# Source_Selection.net
KiCad netlist of a schematic drawn in Altium Designer
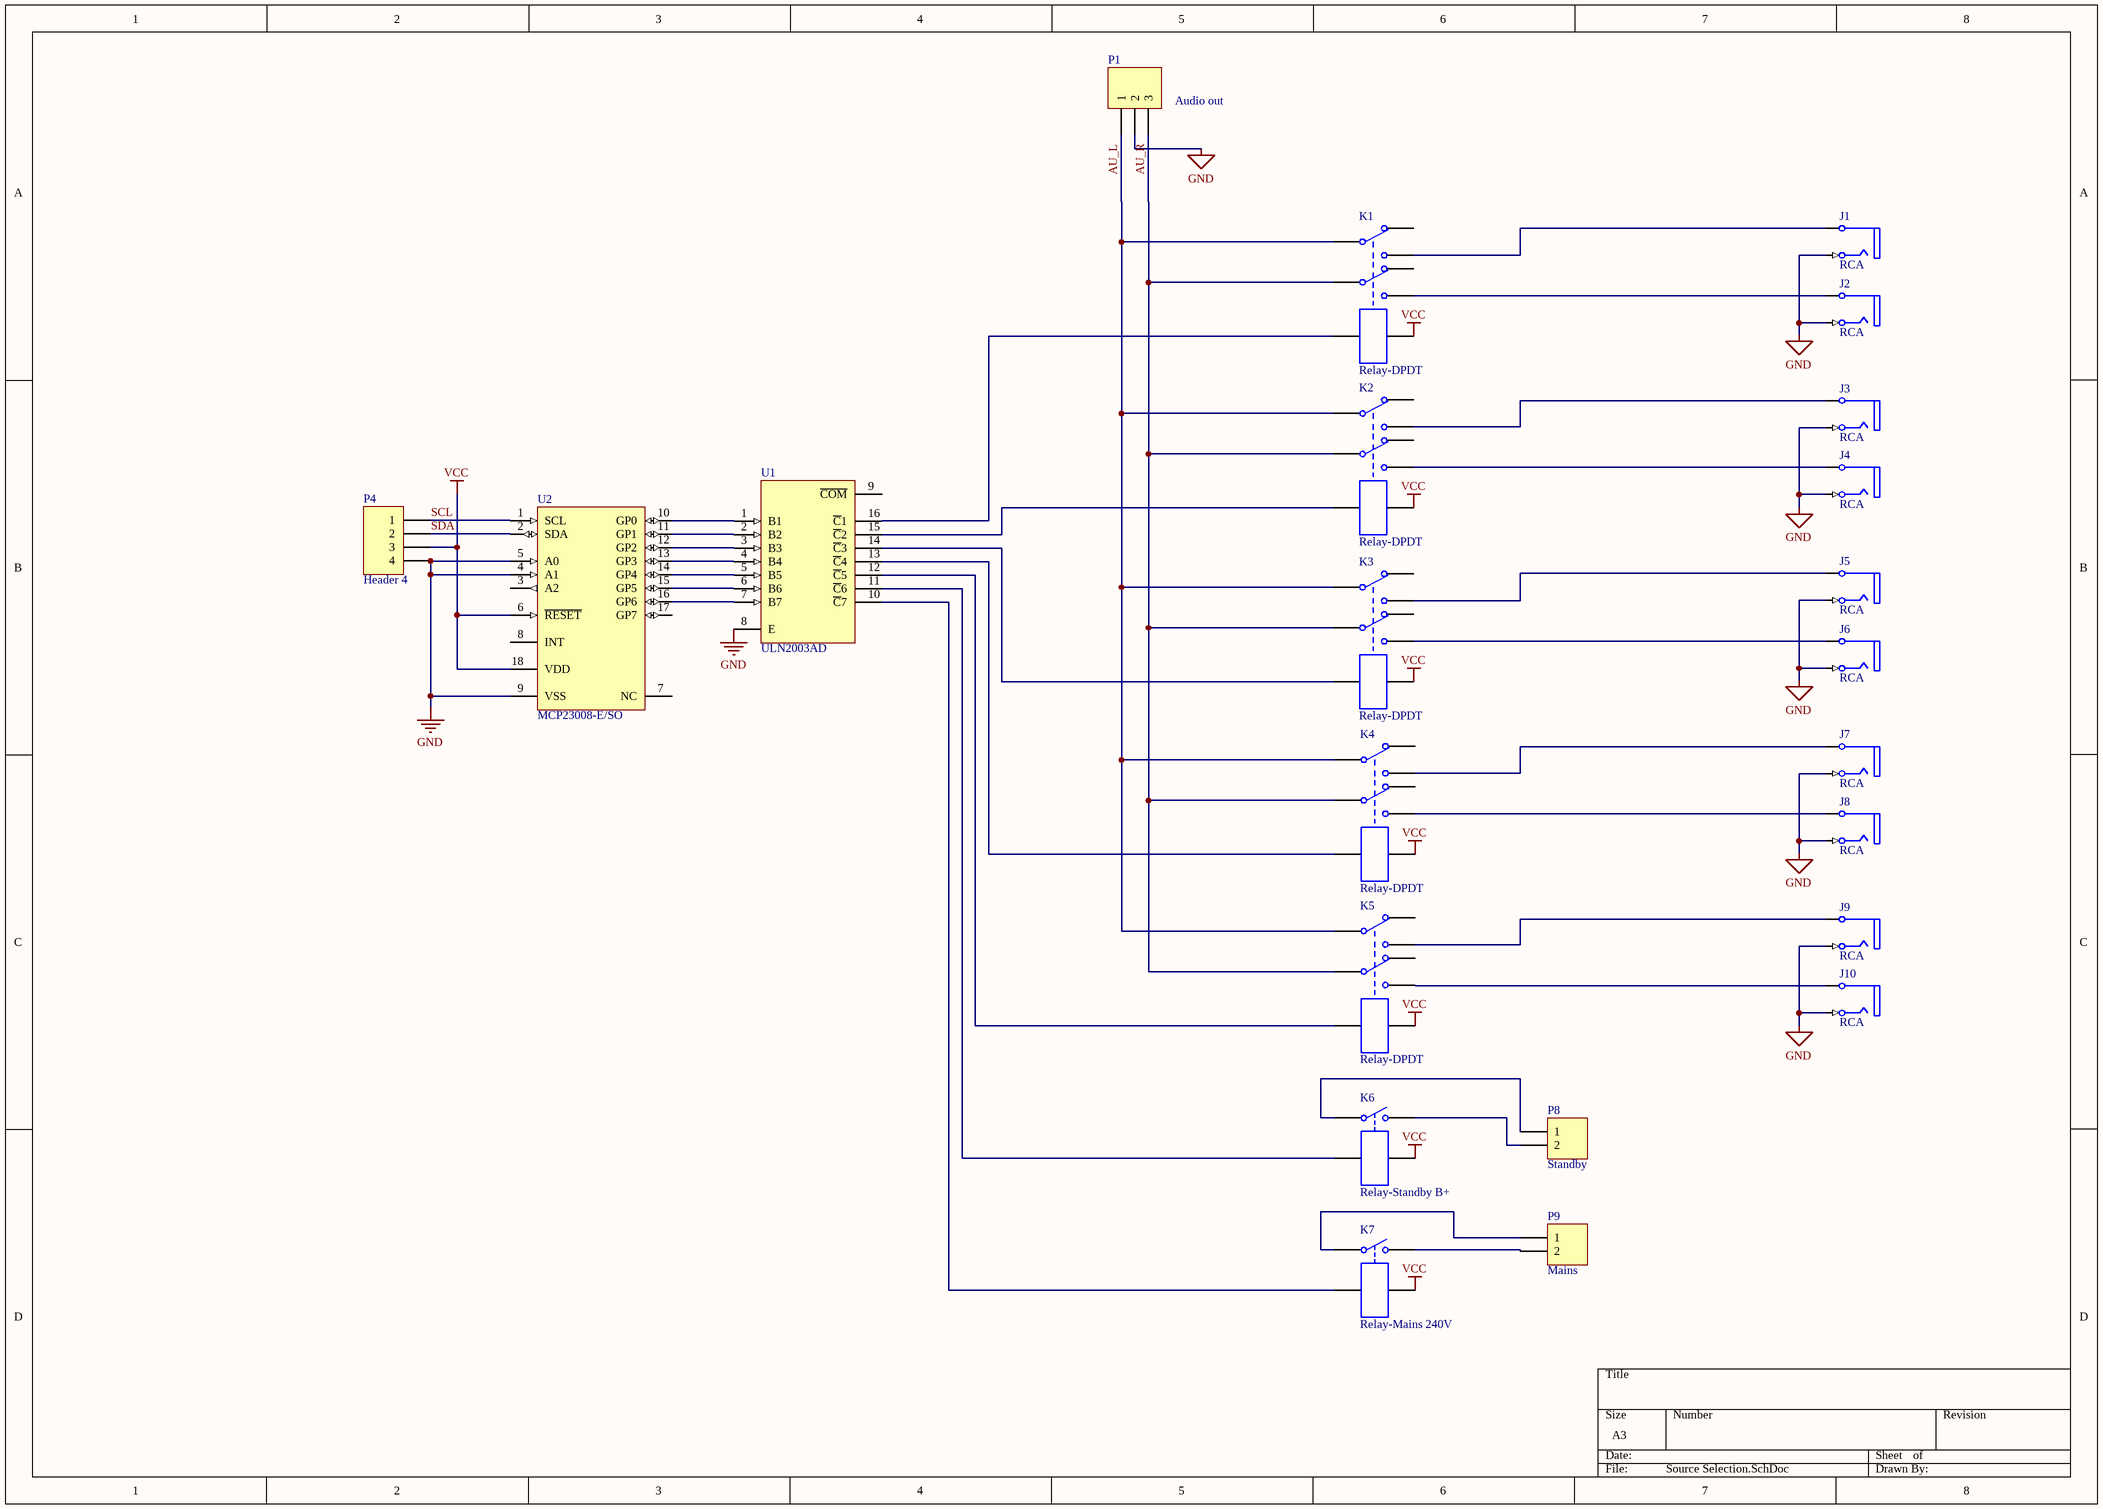
[diagram p0: Source Selection.SchDoc]

(export (version "E")
  (design (tool "Eeschema 10.0.6"))
  (components
    (comp (ref "J1")
      (value "RCA")
      (footprint "RCA/4.5-H2")
      (description "RCA Phono Jack, Right Angle, Thru-Hole, Snap-In")
      (fields (field (name "PUBLISHER") "Altium Limited"))
      (libsource (lib "Miscellaneous Connectors") (part "RCA"))
    )
    (comp (ref "J2")
      (value "RCA")
      (footprint "RCA/4.5-H2")
      (description "RCA Phono Jack, Right Angle, Thru-Hole, Snap-In")
      (fields (field (name "PUBLISHER") "Altium Limited"))
      (libsource (lib "Miscellaneous Connectors") (part "RCA"))
    )
    (comp (ref "J3")
      (value "RCA")
      (footprint "RCA/4.5-H2")
      (description "RCA Phono Jack, Right Angle, Thru-Hole, Snap-In")
      (fields (field (name "PUBLISHER") "Altium Limited"))
      (libsource (lib "Miscellaneous Connectors") (part "RCA"))
    )
    (comp (ref "J4")
      (value "RCA")
      (footprint "RCA/4.5-H2")
      (description "RCA Phono Jack, Right Angle, Thru-Hole, Snap-In")
      (fields (field (name "PUBLISHER") "Altium Limited"))
      (libsource (lib "Miscellaneous Connectors") (part "RCA"))
    )
    (comp (ref "J5")
      (value "RCA")
      (footprint "RCA/4.5-H2")
      (description "RCA Phono Jack, Right Angle, Thru-Hole, Snap-In")
      (fields (field (name "PUBLISHER") "Altium Limited"))
      (libsource (lib "Miscellaneous Connectors") (part "RCA"))
    )
    (comp (ref "J6")
      (value "RCA")
      (footprint "RCA/4.5-H2")
      (description "RCA Phono Jack, Right Angle, Thru-Hole, Snap-In")
      (fields (field (name "PUBLISHER") "Altium Limited"))
      (libsource (lib "Miscellaneous Connectors") (part "RCA"))
    )
    (comp (ref "J7")
      (value "RCA")
      (footprint "RCA/4.5-H2")
      (description "RCA Phono Jack, Right Angle, Thru-Hole, Snap-In")
      (fields (field (name "PUBLISHER") "Altium Limited"))
      (libsource (lib "Miscellaneous Connectors") (part "RCA"))
    )
    (comp (ref "J8")
      (value "RCA")
      (footprint "RCA/4.5-H2")
      (description "RCA Phono Jack, Right Angle, Thru-Hole, Snap-In")
      (fields (field (name "PUBLISHER") "Altium Limited"))
      (libsource (lib "Miscellaneous Connectors") (part "RCA"))
    )
    (comp (ref "J9")
      (value "RCA")
      (footprint "RCA/4.5-H2")
      (description "RCA Phono Jack, Right Angle, Thru-Hole, Snap-In")
      (fields (field (name "PUBLISHER") "Altium Limited"))
      (libsource (lib "Miscellaneous Connectors") (part "RCA"))
    )
    (comp (ref "J10")
      (value "RCA")
      (footprint "RCA/4.5-H2")
      (description "RCA Phono Jack, Right Angle, Thru-Hole, Snap-In")
      (fields (field (name "PUBLISHER") "Altium Limited"))
      (libsource (lib "Miscellaneous Connectors") (part "RCA"))
    )
    (comp (ref "K1")
      (value "Relay-DPDT")
      (footprint "DIP-P8")
      (description "Dual-Pole Dual-Throw Relay")
      (fields (field (name "PUBLISHER") "Altium Limited"))
      (libsource (lib "Miscellaneous Devices") (part "Relay-DPDT"))
    )
    (comp (ref "K2")
      (value "Relay-DPDT")
      (footprint "DIP-P8")
      (description "Dual-Pole Dual-Throw Relay")
      (fields (field (name "PUBLISHER") "Altium Limited"))
      (libsource (lib "Miscellaneous Devices") (part "Relay-DPDT"))
    )
    (comp (ref "K3")
      (value "Relay-DPDT")
      (footprint "DIP-P8")
      (description "Dual-Pole Dual-Throw Relay")
      (fields (field (name "PUBLISHER") "Altium Limited"))
      (libsource (lib "Miscellaneous Devices") (part "Relay-DPDT"))
    )
    (comp (ref "K4")
      (value "Relay-DPDT")
      (footprint "DIP-P8")
      (description "Dual-Pole Dual-Throw Relay")
      (fields (field (name "PUBLISHER") "Altium Limited"))
      (libsource (lib "Miscellaneous Devices") (part "Relay-DPDT"))
    )
    (comp (ref "K5")
      (value "Relay-DPDT")
      (footprint "DIP-P8")
      (description "Dual-Pole Dual-Throw Relay")
      (fields (field (name "PUBLISHER") "Altium Limited"))
      (libsource (lib "Miscellaneous Devices") (part "Relay-DPDT"))
    )
    (comp (ref "K6")
      (value "Relay-Standby B+")
      (footprint "MODULE4")
      (description "Single-Pole Single-Throw Relay")
      (fields (field (name "PUBLISHER") "Altium Limited"))
      (libsource (lib "Miscellaneous Devices") (part "Relay-SPST"))
    )
    (comp (ref "K7")
      (value "Relay-Mains 240V")
      (footprint "MODULE4")
      (description "Single-Pole Single-Throw Relay")
      (fields (field (name "PUBLISHER") "Altium Limited"))
      (libsource (lib "Miscellaneous Devices") (part "Relay-SPST"))
    )
    (comp (ref "P1")
      (value "Audio out")
      (footprint "PH_TERM_3")
      (description "Header, 3-Pin")
      (fields (field (name "PUBLISHER") "Altium Limited"))
      (libsource (lib "Miscellaneous Connectors") (part "Header 3"))
    )
    (comp (ref "P4")
      (value "Header 4")
      (footprint "IDC2.54-H10C")
      (description "Header, 4-Pin")
      (fields (field (name "PUBLISHER") "Altium Limited"))
      (libsource (lib "Miscellaneous Connectors") (part "Header 4"))
    )
    (comp (ref "P8")
      (value "Standby")
      (footprint "PH_TERM_2")
      (description "Header, 2-Pin")
      (fields (field (name "PUBLISHER") "Altium Limited"))
      (libsource (lib "Miscellaneous Connectors") (part "Header 2"))
    )
    (comp (ref "P9")
      (value "Mains")
      (footprint "HDR1X2")
      (description "Header, 2-Pin")
      (fields (field (name "PUBLISHER") "Altium Limited"))
      (libsource (lib "Miscellaneous Connectors") (part "Header 2"))
    )
    (comp (ref "U1")
      (value "ULN2003AD")
      (footprint "D016_N")
      (description "Darlington Transistor Array")
      (fields (field (name "PUBLISHER") "Altium Limited"))
      (libsource (lib "TI Interface Darlington Driver") (part "ULN2003AD"))
    )
    (comp (ref "U2")
      (value "MCP23008-E/SO")
      (footprint "SOIC-SO18_N")
      (description "8-Bit I/O Expander with Serial Interface, 18-Pin SOIC, Extended Temperature")
      (fields (field (name "PUBLISHER") "Altium Limited"))
      (libsource (lib "Microchip Interface") (part "MCP23008-E/SO"))
    )
  )
  (nets
    (net (code "1") (name "/AU_L") (class "Default")
      (node (ref "K1") (pin "1") (pinfunction "1_1") (pintype "passive"))
      (node (ref "K2") (pin "1") (pinfunction "1_1") (pintype "passive"))
      (node (ref "K3") (pin "1") (pinfunction "1_1") (pintype "passive"))
      (node (ref "K4") (pin "1") (pinfunction "1_1") (pintype "passive"))
      (node (ref "K5") (pin "1") (pinfunction "1_1") (pintype "passive"))
      (node (ref "P1") (pin "1") (pinfunction "1_1") (pintype "passive"))
    )
    (net (code "2") (name "/AU_R") (class "Default")
      (node (ref "K1") (pin "4") (pinfunction "4_4") (pintype "passive"))
      (node (ref "K2") (pin "4") (pinfunction "4_4") (pintype "passive"))
      (node (ref "K3") (pin "4") (pinfunction "4_4") (pintype "passive"))
      (node (ref "K4") (pin "4") (pinfunction "4_4") (pintype "passive"))
      (node (ref "K5") (pin "4") (pinfunction "4_4") (pintype "passive"))
      (node (ref "P1") (pin "3") (pinfunction "3_3") (pintype "passive"))
    )
    (net (code "3") (name "/SCL") (class "Default")
      (node (ref "P4") (pin "1") (pinfunction "1_1") (pintype "passive"))
      (node (ref "U2") (pin "1") (pinfunction "SCL_1") (pintype "input"))
    )
    (net (code "4") (name "/SDA") (class "Default")
      (node (ref "P4") (pin "2") (pinfunction "2_2") (pintype "passive"))
      (node (ref "U2") (pin "2") (pinfunction "SDA_2") (pintype "bidirectional"))
    )
    (net (code "5") (name "GND") (class "Default")
      (node (ref "J1") (pin "2B") (pinfunction "Signal_2B") (pintype "input"))
      (node (ref "J10") (pin "2B") (pinfunction "Signal_2B") (pintype "input"))
      (node (ref "J2") (pin "2B") (pinfunction "Signal_2B") (pintype "input"))
      (node (ref "J3") (pin "2B") (pinfunction "Signal_2B") (pintype "input"))
      (node (ref "J4") (pin "2B") (pinfunction "Signal_2B") (pintype "input"))
      (node (ref "J5") (pin "2B") (pinfunction "Signal_2B") (pintype "input"))
      (node (ref "J6") (pin "2B") (pinfunction "Signal_2B") (pintype "input"))
      (node (ref "J7") (pin "2B") (pinfunction "Signal_2B") (pintype "input"))
      (node (ref "J8") (pin "2B") (pinfunction "Signal_2B") (pintype "input"))
      (node (ref "J9") (pin "2B") (pinfunction "Signal_2B") (pintype "input"))
      (node (ref "P1") (pin "2") (pinfunction "2_2") (pintype "passive"))
      (node (ref "P4") (pin "4") (pinfunction "4_4") (pintype "passive"))
      (node (ref "U1") (pin "8") (pinfunction "E_8") (pintype "power_in"))
      (node (ref "U2") (pin "4") (pinfunction "A1_4") (pintype "input"))
      (node (ref "U2") (pin "5") (pinfunction "A0_5") (pintype "input"))
      (node (ref "U2") (pin "9") (pinfunction "VSS_9") (pintype "power_in"))
    )
    (net (code "6") (name "Net-(J1-Ground)") (class "Default")
      (node (ref "J1") (pin "1A") (pinfunction "Ground_1A") (pintype "power_in"))
      (node (ref "K1") (pin "3") (pinfunction "3_3") (pintype "passive"))
    )
    (net (code "7") (name "Net-(J2-Ground)") (class "Default")
      (node (ref "J2") (pin "1A") (pinfunction "Ground_1A") (pintype "power_in"))
      (node (ref "K1") (pin "6") (pinfunction "6_6") (pintype "passive"))
    )
    (net (code "8") (name "Net-(J3-Ground)") (class "Default")
      (node (ref "J3") (pin "1A") (pinfunction "Ground_1A") (pintype "power_in"))
      (node (ref "K2") (pin "3") (pinfunction "3_3") (pintype "passive"))
    )
    (net (code "9") (name "Net-(J4-Ground)") (class "Default")
      (node (ref "J4") (pin "1A") (pinfunction "Ground_1A") (pintype "power_in"))
      (node (ref "K2") (pin "6") (pinfunction "6_6") (pintype "passive"))
    )
    (net (code "10") (name "Net-(J5-Ground)") (class "Default")
      (node (ref "J5") (pin "1A") (pinfunction "Ground_1A") (pintype "power_in"))
      (node (ref "K3") (pin "3") (pinfunction "3_3") (pintype "passive"))
    )
    (net (code "11") (name "Net-(J6-Ground)") (class "Default")
      (node (ref "J6") (pin "1A") (pinfunction "Ground_1A") (pintype "power_in"))
      (node (ref "K3") (pin "6") (pinfunction "6_6") (pintype "passive"))
    )
    (net (code "12") (name "Net-(J7-Ground)") (class "Default")
      (node (ref "J7") (pin "1A") (pinfunction "Ground_1A") (pintype "power_in"))
      (node (ref "K4") (pin "3") (pinfunction "3_3") (pintype "passive"))
    )
    (net (code "13") (name "Net-(J8-Ground)") (class "Default")
      (node (ref "J8") (pin "1A") (pinfunction "Ground_1A") (pintype "power_in"))
      (node (ref "K4") (pin "6") (pinfunction "6_6") (pintype "passive"))
    )
    (net (code "14") (name "Net-(J9-Ground)") (class "Default")
      (node (ref "J9") (pin "1A") (pinfunction "Ground_1A") (pintype "power_in"))
      (node (ref "K5") (pin "3") (pinfunction "3_3") (pintype "passive"))
    )
    (net (code "15") (name "Net-(J10-Ground)") (class "Default")
      (node (ref "J10") (pin "1A") (pinfunction "Ground_1A") (pintype "power_in"))
      (node (ref "K5") (pin "6") (pinfunction "6_6") (pintype "passive"))
    )
    (net (code "16") (name "Net-(K6-Pad1)") (class "Default")
      (node (ref "K6") (pin "1") (pinfunction "1_1") (pintype "passive"))
      (node (ref "P8") (pin "1") (pinfunction "1_1") (pintype "passive"))
    )
    (net (code "17") (name "Net-(K6-Pad2)") (class "Default")
      (node (ref "K6") (pin "2") (pinfunction "2_2") (pintype "passive"))
      (node (ref "P8") (pin "2") (pinfunction "2_2") (pintype "passive"))
    )
    (net (code "18") (name "Net-(K7-Pad1)") (class "Default")
      (node (ref "K7") (pin "1") (pinfunction "1_1") (pintype "passive"))
      (node (ref "P9") (pin "1") (pinfunction "1_1") (pintype "passive"))
    )
    (net (code "19") (name "Net-(K7-Pad2)") (class "Default")
      (node (ref "K7") (pin "2") (pinfunction "2_2") (pintype "passive"))
      (node (ref "P9") (pin "2") (pinfunction "2_2") (pintype "passive"))
    )
    (net (code "20") (name "Net-(U1-B1)") (class "Default")
      (node (ref "U1") (pin "1") (pinfunction "B1_1") (pintype "input"))
      (node (ref "U2") (pin "10") (pinfunction "GP0_10") (pintype "bidirectional"))
    )
    (net (code "21") (name "Net-(U1-B2)") (class "Default")
      (node (ref "U1") (pin "2") (pinfunction "B2_2") (pintype "input"))
      (node (ref "U2") (pin "11") (pinfunction "GP1_11") (pintype "bidirectional"))
    )
    (net (code "22") (name "Net-(U1-B3)") (class "Default")
      (node (ref "U1") (pin "3") (pinfunction "B3_3") (pintype "input"))
      (node (ref "U2") (pin "12") (pinfunction "GP2_12") (pintype "bidirectional"))
    )
    (net (code "23") (name "Net-(U1-B4)") (class "Default")
      (node (ref "U1") (pin "4") (pinfunction "B4_4") (pintype "input"))
      (node (ref "U2") (pin "13") (pinfunction "GP3_13") (pintype "bidirectional"))
    )
    (net (code "24") (name "Net-(U1-B5)") (class "Default")
      (node (ref "U1") (pin "5") (pinfunction "B5_5") (pintype "input"))
      (node (ref "U2") (pin "14") (pinfunction "GP4_14") (pintype "bidirectional"))
    )
    (net (code "25") (name "Net-(U1-B6)") (class "Default")
      (node (ref "U1") (pin "6") (pinfunction "B6_6") (pintype "input"))
      (node (ref "U2") (pin "15") (pinfunction "GP5_15") (pintype "bidirectional"))
    )
    (net (code "26") (name "Net-(U1-B7)") (class "Default")
      (node (ref "U1") (pin "7") (pinfunction "B7_7") (pintype "input"))
      (node (ref "U2") (pin "16") (pinfunction "GP6_16") (pintype "bidirectional"))
    )
    (net (code "27") (name "Net-(U1-~{C}1)") (class "Default")
      (node (ref "K1") (pin "7") (pinfunction "7_7") (pintype "passive"))
      (node (ref "U1") (pin "16") (pinfunction "~{C}1_16") (pintype "open_collector"))
    )
    (net (code "28") (name "Net-(U1-~{C}2)") (class "Default")
      (node (ref "K2") (pin "7") (pinfunction "7_7") (pintype "passive"))
      (node (ref "U1") (pin "15") (pinfunction "~{C}2_15") (pintype "open_collector"))
    )
    (net (code "29") (name "Net-(U1-~{C}3)") (class "Default")
      (node (ref "K3") (pin "7") (pinfunction "7_7") (pintype "passive"))
      (node (ref "U1") (pin "14") (pinfunction "~{C}3_14") (pintype "open_collector"))
    )
    (net (code "30") (name "Net-(U1-~{C}4)") (class "Default")
      (node (ref "K4") (pin "7") (pinfunction "7_7") (pintype "passive"))
      (node (ref "U1") (pin "13") (pinfunction "~{C}4_13") (pintype "open_collector"))
    )
    (net (code "31") (name "Net-(U1-~{C}5)") (class "Default")
      (node (ref "K5") (pin "7") (pinfunction "7_7") (pintype "passive"))
      (node (ref "U1") (pin "12") (pinfunction "~{C}5_12") (pintype "open_collector"))
    )
    (net (code "32") (name "Net-(U1-~{C}6)") (class "Default")
      (node (ref "K6") (pin "3") (pinfunction "3_3") (pintype "passive"))
      (node (ref "U1") (pin "11") (pinfunction "~{C}6_11") (pintype "open_collector"))
    )
    (net (code "33") (name "Net-(U1-~{C}7)") (class "Default")
      (node (ref "K7") (pin "3") (pinfunction "3_3") (pintype "passive"))
      (node (ref "U1") (pin "10") (pinfunction "~{C}7_10") (pintype "open_collector"))
    )
    (net (code "34") (name "VCC") (class "Default")
      (node (ref "K1") (pin "8") (pinfunction "8_8") (pintype "passive"))
      (node (ref "K2") (pin "8") (pinfunction "8_8") (pintype "passive"))
      (node (ref "K3") (pin "8") (pinfunction "8_8") (pintype "passive"))
      (node (ref "K4") (pin "8") (pinfunction "8_8") (pintype "passive"))
      (node (ref "K5") (pin "8") (pinfunction "8_8") (pintype "passive"))
      (node (ref "K6") (pin "4") (pinfunction "4_4") (pintype "passive"))
      (node (ref "K7") (pin "4") (pinfunction "4_4") (pintype "passive"))
      (node (ref "P4") (pin "3") (pinfunction "3_3") (pintype "passive"))
      (node (ref "U2") (pin "18") (pinfunction "VDD_18") (pintype "power_in"))
      (node (ref "U2") (pin "6") (pinfunction "~{RESET}_6") (pintype "input"))
    )
    (net (code "35") (name "unconnected-(K1-Pad2)") (class "Default")
      (node (ref "K1") (pin "2") (pinfunction "2_2") (pintype "passive"))
    )
    (net (code "36") (name "unconnected-(K1-Pad5)") (class "Default")
      (node (ref "K1") (pin "5") (pinfunction "5_5") (pintype "passive"))
    )
    (net (code "37") (name "unconnected-(K2-Pad2)") (class "Default")
      (node (ref "K2") (pin "2") (pinfunction "2_2") (pintype "passive"))
    )
    (net (code "38") (name "unconnected-(K2-Pad5)") (class "Default")
      (node (ref "K2") (pin "5") (pinfunction "5_5") (pintype "passive"))
    )
    (net (code "39") (name "unconnected-(K3-Pad2)") (class "Default")
      (node (ref "K3") (pin "2") (pinfunction "2_2") (pintype "passive"))
    )
    (net (code "40") (name "unconnected-(K3-Pad5)") (class "Default")
      (node (ref "K3") (pin "5") (pinfunction "5_5") (pintype "passive"))
    )
    (net (code "41") (name "unconnected-(K4-Pad2)") (class "Default")
      (node (ref "K4") (pin "2") (pinfunction "2_2") (pintype "passive"))
    )
    (net (code "42") (name "unconnected-(K4-Pad5)") (class "Default")
      (node (ref "K4") (pin "5") (pinfunction "5_5") (pintype "passive"))
    )
    (net (code "43") (name "unconnected-(K5-Pad2)") (class "Default")
      (node (ref "K5") (pin "2") (pinfunction "2_2") (pintype "passive"))
    )
    (net (code "44") (name "unconnected-(K5-Pad5)") (class "Default")
      (node (ref "K5") (pin "5") (pinfunction "5_5") (pintype "passive"))
    )
    (net (code "45") (name "unconnected-(U1-~{COM}-Pad9)") (class "Default")
      (node (ref "U1") (pin "9") (pinfunction "~{COM}_9") (pintype "passive"))
    )
    (net (code "46") (name "unconnected-(U2-A2-Pad3)") (class "Default")
      (node (ref "U2") (pin "3") (pinfunction "A2_3") (pintype "output"))
    )
    (net (code "47") (name "unconnected-(U2-GP7-Pad17)") (class "Default")
      (node (ref "U2") (pin "17") (pinfunction "GP7_17") (pintype "bidirectional"))
    )
    (net (code "48") (name "unconnected-(U2-INT-Pad8)") (class "Default")
      (node (ref "U2") (pin "8") (pinfunction "INT_8") (pintype "open_collector"))
    )
    (net (code "49") (name "unconnected-(U2-NC-Pad7)") (class "Default")
      (node (ref "U2") (pin "7") (pinfunction "NC_7") (pintype "passive"))
    )
  )
)
